# KUBODriver_Amp.net
KiCad netlist of a schematic drawn in Altium Designer
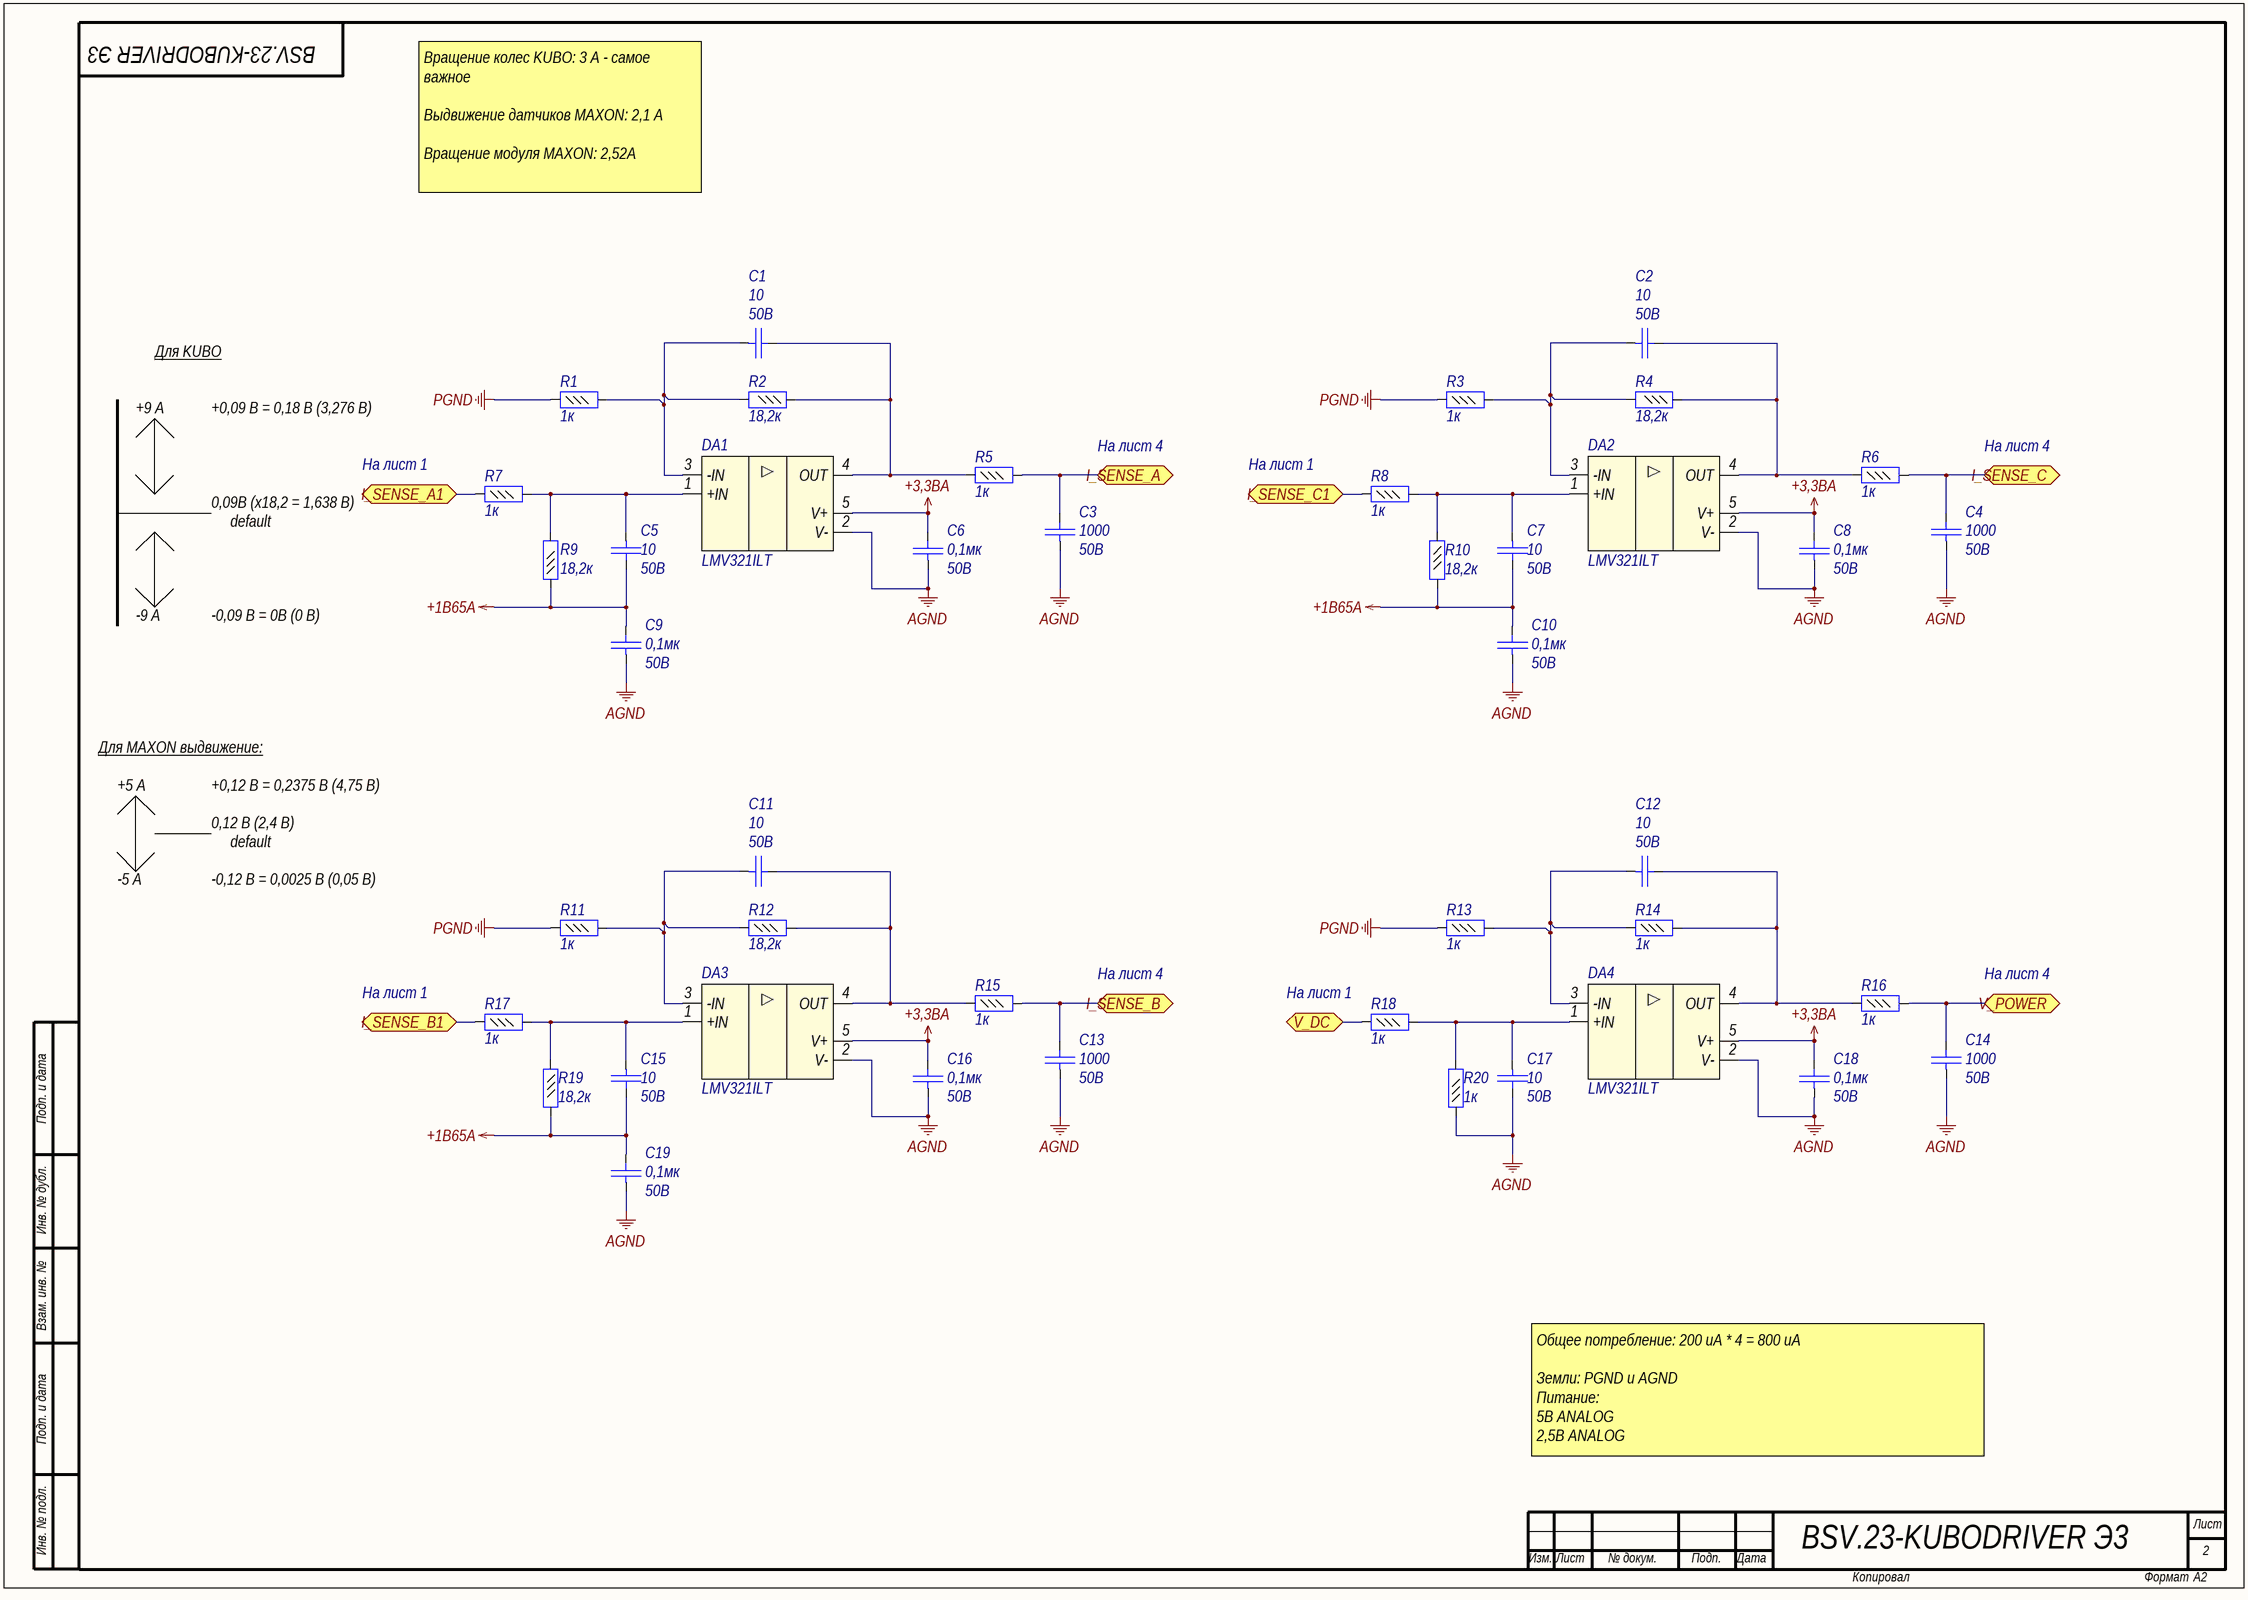
[diagram p0: KUBODriver_Amp.SchDoc]

(export (version "E")
  (design (tool "Eeschema 10.0.6"))
  (components
    (comp (ref "C1")
      (value "10")
      (footprint "C0402")
      (description "Конденсатор")
      (fields
        (field (name "VOLTAGE") "50B")
        (field (name "PART NUMBER") "GRM1535C1H100J")
        (field (name "Comment") "Capacitor")
      )
      (libsource (lib "MOP44") (part "Capacitor"))
    )
    (comp (ref "C2")
      (value "10")
      (footprint "C0402")
      (description "Конденсатор")
      (fields
        (field (name "VOLTAGE") "50B")
        (field (name "PART NUMBER") "GRM1535C1H100J")
        (field (name "Comment") "Capacitor")
      )
      (libsource (lib "MOP44") (part "Capacitor"))
    )
    (comp (ref "C3")
      (value "1000")
      (footprint "C0402")
      (description "Конденсатор")
      (fields
        (field (name "VOLTAGE") "50B")
        (field (name "PART NUMBER") "GRM1555C1H102J")
        (field (name "Comment") "Capacitor")
      )
      (libsource (lib "MOP44") (part "Capacitor"))
    )
    (comp (ref "C4")
      (value "1000")
      (footprint "C0402")
      (description "Конденсатор")
      (fields
        (field (name "VOLTAGE") "50B")
        (field (name "PART NUMBER") "GRM1555C1H102J")
        (field (name "Comment") "Capacitor")
      )
      (libsource (lib "MOP44") (part "Capacitor"))
    )
    (comp (ref "C5")
      (value "10")
      (footprint "C0402")
      (description "Конденсатор")
      (fields
        (field (name "VOLTAGE") "50B")
        (field (name "PART NUMBER") "GRM1535C1H100J")
        (field (name "Comment") "Capacitor")
      )
      (libsource (lib "MOP44") (part "Capacitor"))
    )
    (comp (ref "C6")
      (value "0,1мк")
      (footprint "C0402")
      (description "Конденсатор")
      (fields
        (field (name "VOLTAGE") "50В")
        (field (name "PART NUMBER") "GRM155R71H104KE14D ")
        (field (name "Comment") "Capacitor")
      )
      (libsource (lib "MOP44") (part "Capacitor"))
    )
    (comp (ref "C7")
      (value "10")
      (footprint "C0402")
      (description "Конденсатор")
      (fields
        (field (name "VOLTAGE") "50B")
        (field (name "PART NUMBER") "GRM1535C1H100J")
        (field (name "Comment") "Capacitor")
      )
      (libsource (lib "MOP44") (part "Capacitor"))
    )
    (comp (ref "C8")
      (value "0,1мк")
      (footprint "C0402")
      (description "Конденсатор")
      (fields
        (field (name "VOLTAGE") "50В")
        (field (name "PART NUMBER") "GRM155R71H104KE14D ")
        (field (name "Comment") "Capacitor")
      )
      (libsource (lib "MOP44") (part "Capacitor"))
    )
    (comp (ref "C9")
      (value "0,1мк")
      (footprint "C0402")
      (description "Конденсатор")
      (fields
        (field (name "VOLTAGE") "50В")
        (field (name "PART NUMBER") "GRM155R71H104KE14D ")
        (field (name "Comment") "Capacitor")
      )
      (libsource (lib "MOP44") (part "Capacitor"))
    )
    (comp (ref "C10")
      (value "0,1мк")
      (footprint "C0402")
      (description "Конденсатор")
      (fields
        (field (name "VOLTAGE") "50В")
        (field (name "PART NUMBER") "GRM155R71H104KE14D ")
        (field (name "Comment") "Capacitor")
      )
      (libsource (lib "MOP44") (part "Capacitor"))
    )
    (comp (ref "C11")
      (value "10")
      (footprint "C0402")
      (description "Конденсатор")
      (fields
        (field (name "VOLTAGE") "50B")
        (field (name "PART NUMBER") "GRM1535C1H100J")
        (field (name "Comment") "Capacitor")
      )
      (libsource (lib "MOP44") (part "Capacitor"))
    )
    (comp (ref "C12")
      (value "10")
      (footprint "C0402")
      (description "Конденсатор")
      (fields
        (field (name "VOLTAGE") "50B")
        (field (name "PART NUMBER") "GRM1535C1H100J")
        (field (name "Comment") "Capacitor")
      )
      (libsource (lib "MOP44") (part "Capacitor"))
    )
    (comp (ref "C13")
      (value "1000")
      (footprint "C0402")
      (description "Конденсатор")
      (fields
        (field (name "VOLTAGE") "50B")
        (field (name "PART NUMBER") "GRM1555C1H102J")
        (field (name "Comment") "Capacitor")
      )
      (libsource (lib "MOP44") (part "Capacitor"))
    )
    (comp (ref "C14")
      (value "1000")
      (footprint "C0402")
      (description "Конденсатор")
      (fields
        (field (name "VOLTAGE") "50B")
        (field (name "PART NUMBER") "GRM1555C1H102J")
        (field (name "Comment") "Capacitor")
      )
      (libsource (lib "MOP44") (part "Capacitor"))
    )
    (comp (ref "C15")
      (value "10")
      (footprint "C0402")
      (description "Конденсатор")
      (fields
        (field (name "VOLTAGE") "50B")
        (field (name "PART NUMBER") "GRM1535C1H100J")
        (field (name "Comment") "Capacitor")
      )
      (libsource (lib "MOP44") (part "Capacitor"))
    )
    (comp (ref "C16")
      (value "0,1мк")
      (footprint "C0402")
      (description "Конденсатор")
      (fields
        (field (name "VOLTAGE") "50В")
        (field (name "PART NUMBER") "GRM155R71H104KE14D ")
        (field (name "Comment") "Capacitor")
      )
      (libsource (lib "MOP44") (part "Capacitor"))
    )
    (comp (ref "C17")
      (value "10")
      (footprint "C0402")
      (description "Конденсатор")
      (fields
        (field (name "VOLTAGE") "50B")
        (field (name "PART NUMBER") "GRM1535C1H100J")
        (field (name "Comment") "Capacitor")
      )
      (libsource (lib "MOP44") (part "Capacitor"))
    )
    (comp (ref "C18")
      (value "0,1мк")
      (footprint "C0402")
      (description "Конденсатор")
      (fields
        (field (name "VOLTAGE") "50В")
        (field (name "PART NUMBER") "GRM155R71H104KE14D ")
        (field (name "Comment") "Capacitor")
      )
      (libsource (lib "MOP44") (part "Capacitor"))
    )
    (comp (ref "C19")
      (value "0,1мк")
      (footprint "C0402")
      (description "Конденсатор")
      (fields
        (field (name "VOLTAGE") "50В")
        (field (name "PART NUMBER") "GRM155R71H104KE14D ")
        (field (name "Comment") "Capacitor")
      )
      (libsource (lib "MOP44") (part "Capacitor"))
    )
    (comp (ref "DA1")
      (value "LMV321ILT")
      (footprint "SOT23-5")
      (description "HIGH-DRIVE OPERATIONAL AMPLIFIERS WITH SHUTDOWN")
      (libsource (lib "MOP44") (part "LMV321ILT"))
    )
    (comp (ref "DA2")
      (value "LMV321ILT")
      (footprint "SOT23-5")
      (description "HIGH-DRIVE OPERATIONAL AMPLIFIERS WITH SHUTDOWN")
      (libsource (lib "MOP44") (part "LMV321ILT"))
    )
    (comp (ref "DA3")
      (value "LMV321ILT")
      (footprint "SOT23-5")
      (description "HIGH-DRIVE OPERATIONAL AMPLIFIERS WITH SHUTDOWN")
      (libsource (lib "MOP44") (part "LMV321ILT"))
    )
    (comp (ref "DA4")
      (value "LMV321ILT")
      (footprint "SOT23-5")
      (description "HIGH-DRIVE OPERATIONAL AMPLIFIERS WITH SHUTDOWN")
      (libsource (lib "MOP44") (part "LMV321ILT"))
    )
    (comp (ref "R1")
      (value "1к")
      (footprint "R0402")
      (description "Резистор")
      (fields (field (name "PART NUMBER") "RC0402FR-071KL") (field (name "POWER") "0,062Вт"))
      (libsource (lib "MOP44") (part "Resistor_0,062Вт"))
    )
    (comp (ref "R2")
      (value "18,2к")
      (footprint "R0402")
      (description "Резистор")
      (fields (field (name "PART NUMBER") "RC0402FR-0718K2L") (field (name "POWER") "0,062Вт"))
      (libsource (lib "") (part "Resistor_0,062Вт_1"))
    )
    (comp (ref "R3")
      (value "1к")
      (footprint "R0402")
      (description "Резистор")
      (fields (field (name "PART NUMBER") "RC0402FR-071KL") (field (name "POWER") "0,062Вт"))
      (libsource (lib "MOP44") (part "Resistor_0,062Вт"))
    )
    (comp (ref "R4")
      (value "18,2к")
      (footprint "R0402")
      (description "Резистор")
      (fields (field (name "PART NUMBER") "RC0402FR-0718K2L") (field (name "POWER") "0,062Вт"))
      (libsource (lib "") (part "Resistor_0,062Вт_1"))
    )
    (comp (ref "R5")
      (value "1к")
      (footprint "R0402")
      (description "Резистор")
      (fields (field (name "PART NUMBER") "RC0402FR-071KL") (field (name "POWER") "0,062Вт"))
      (libsource (lib "MOP44") (part "Resistor_0,062Вт"))
    )
    (comp (ref "R6")
      (value "1к")
      (footprint "R0402")
      (description "Резистор")
      (fields (field (name "PART NUMBER") "RC0402FR-071KL") (field (name "POWER") "0,062Вт"))
      (libsource (lib "MOP44") (part "Resistor_0,062Вт"))
    )
    (comp (ref "R7")
      (value "1к")
      (footprint "R0402")
      (description "Резистор")
      (fields (field (name "PART NUMBER") "RC0402FR-071KL") (field (name "POWER") "0,062Вт"))
      (libsource (lib "MOP44") (part "Resistor_0,062Вт"))
    )
    (comp (ref "R8")
      (value "1к")
      (footprint "R0402")
      (description "Резистор")
      (fields (field (name "PART NUMBER") "RC0402FR-071KL") (field (name "POWER") "0,062Вт"))
      (libsource (lib "MOP44") (part "Resistor_0,062Вт"))
    )
    (comp (ref "R9")
      (value "18,2к")
      (footprint "R0402")
      (description "Резистор")
      (fields (field (name "PART NUMBER") "RC0402FR-0718K2L") (field (name "POWER") "0,062Вт"))
      (libsource (lib "") (part "Resistor_0,062Вт_3"))
    )
    (comp (ref "R10")
      (value "18,2к")
      (footprint "R0402")
      (description "Резистор")
      (fields (field (name "PART NUMBER") "RC0402FR-0718K2L") (field (name "POWER") "0,062Вт"))
      (libsource (lib "") (part "Resistor_0,062Вт_2"))
    )
    (comp (ref "R11")
      (value "1к")
      (footprint "R0402")
      (description "Резистор")
      (fields (field (name "PART NUMBER") "RC0402FR-071KL") (field (name "POWER") "0,062Вт"))
      (libsource (lib "MOP44") (part "Resistor_0,062Вт"))
    )
    (comp (ref "R12")
      (value "18,2к")
      (footprint "R0402")
      (description "Резистор")
      (fields (field (name "PART NUMBER") "RC0402FR-0718K2L") (field (name "POWER") "0,062Вт"))
      (libsource (lib "MOP44") (part "Resistor_0,062Вт"))
    )
    (comp (ref "R13")
      (value "1к")
      (footprint "R0402")
      (description "Резистор")
      (fields (field (name "PART NUMBER") "RC0402FR-071KL") (field (name "POWER") "0,062Вт"))
      (libsource (lib "MOP44") (part "Resistor_0,062Вт"))
    )
    (comp (ref "R14")
      (value "1к")
      (footprint "R0402")
      (description "Резистор")
      (fields (field (name "PART NUMBER") "RC0402FR-071KL") (field (name "POWER") "0,062Вт"))
      (libsource (lib "MOP44") (part "Resistor_0,062Вт"))
    )
    (comp (ref "R15")
      (value "1к")
      (footprint "R0402")
      (description "Резистор")
      (fields (field (name "PART NUMBER") "RC0402FR-071KL") (field (name "POWER") "0,062Вт"))
      (libsource (lib "MOP44") (part "Resistor_0,062Вт"))
    )
    (comp (ref "R16")
      (value "1к")
      (footprint "R0402")
      (description "Резистор")
      (fields (field (name "PART NUMBER") "RC0402FR-071KL") (field (name "POWER") "0,062Вт"))
      (libsource (lib "MOP44") (part "Resistor_0,062Вт"))
    )
    (comp (ref "R17")
      (value "1к")
      (footprint "R0402")
      (description "Резистор")
      (fields (field (name "PART NUMBER") "RC0402FR-071KL") (field (name "POWER") "0,062Вт"))
      (libsource (lib "MOP44") (part "Resistor_0,062Вт"))
    )
    (comp (ref "R18")
      (value "1к")
      (footprint "R0402")
      (description "Резистор")
      (fields (field (name "PART NUMBER") "RC0402FR-071KL") (field (name "POWER") "0,062Вт"))
      (libsource (lib "MOP44") (part "Resistor_0,062Вт"))
    )
    (comp (ref "R19")
      (value "18,2к")
      (footprint "R0402")
      (description "Резистор")
      (fields (field (name "PART NUMBER") "RC0402FR-0718K2L") (field (name "POWER") "0,062Вт"))
      (libsource (lib "") (part "Resistor_0,062Вт_2"))
    )
    (comp (ref "R20")
      (value "1к")
      (footprint "R0402")
      (description "Резистор")
      (fields (field (name "PART NUMBER") "RC0402FR-071KL") (field (name "POWER") "0,062Вт"))
      (libsource (lib "") (part "Resistor_0,062Вт_3"))
    )
  )
  (nets
    (net (code "1") (name "+1B65A") (class "Default")
      (node (ref "C10") (pin "2") (pinfunction "2_2") (pintype "passive"))
      (node (ref "C15") (pin "2") (pinfunction "2_2") (pintype "passive"))
      (node (ref "C19") (pin "2") (pinfunction "2_2") (pintype "passive"))
      (node (ref "C5") (pin "2") (pinfunction "2_2") (pintype "passive"))
      (node (ref "C7") (pin "2") (pinfunction "2_2") (pintype "passive"))
      (node (ref "C9") (pin "2") (pinfunction "2_2") (pintype "passive"))
      (node (ref "R10") (pin "2") (pinfunction "2_2") (pintype "passive"))
      (node (ref "R19") (pin "2") (pinfunction "2_2") (pintype "passive"))
      (node (ref "R9") (pin "1") (pinfunction "1_1") (pintype "passive"))
    )
    (net (code "2") (name "+3,3BA") (class "Default")
      (node (ref "C16") (pin "2") (pinfunction "2_2") (pintype "passive"))
      (node (ref "C18") (pin "2") (pinfunction "2_2") (pintype "passive"))
      (node (ref "C6") (pin "2") (pinfunction "2_2") (pintype "passive"))
      (node (ref "C8") (pin "2") (pinfunction "2_2") (pintype "passive"))
      (node (ref "DA1") (pin "5") (pinfunction "V+_5") (pintype "passive"))
      (node (ref "DA2") (pin "5") (pinfunction "V+_5") (pintype "passive"))
      (node (ref "DA3") (pin "5") (pinfunction "V+_5") (pintype "passive"))
      (node (ref "DA4") (pin "5") (pinfunction "V+_5") (pintype "passive"))
    )
    (net (code "3") (name "/I_SENSE_A") (class "Default")
      (node (ref "C3") (pin "2") (pinfunction "2_2") (pintype "passive"))
      (node (ref "R5") (pin "2") (pinfunction "2_2") (pintype "passive"))
    )
    (net (code "4") (name "/I_SENSE_A1") (class "Default")
      (node (ref "R7") (pin "1") (pinfunction "1_1") (pintype "passive"))
    )
    (net (code "5") (name "/I_SENSE_B") (class "Default")
      (node (ref "C13") (pin "2") (pinfunction "2_2") (pintype "passive"))
      (node (ref "R15") (pin "2") (pinfunction "2_2") (pintype "passive"))
    )
    (net (code "6") (name "/I_SENSE_B1") (class "Default")
      (node (ref "R17") (pin "1") (pinfunction "1_1") (pintype "passive"))
    )
    (net (code "7") (name "/I_SENSE_C") (class "Default")
      (node (ref "C4") (pin "2") (pinfunction "2_2") (pintype "passive"))
      (node (ref "R6") (pin "2") (pinfunction "2_2") (pintype "passive"))
    )
    (net (code "8") (name "/I_SENSE_C1") (class "Default")
      (node (ref "R8") (pin "1") (pinfunction "1_1") (pintype "passive"))
    )
    (net (code "9") (name "/V_DC") (class "Default")
      (node (ref "R18") (pin "1") (pinfunction "1_1") (pintype "passive"))
    )
    (net (code "10") (name "/V_POWER") (class "Default")
      (node (ref "C14") (pin "2") (pinfunction "2_2") (pintype "passive"))
      (node (ref "R16") (pin "2") (pinfunction "2_2") (pintype "passive"))
    )
    (net (code "11") (name "AGND") (class "Default")
      (node (ref "C10") (pin "1") (pinfunction "1_1") (pintype "passive"))
      (node (ref "C13") (pin "1") (pinfunction "1_1") (pintype "passive"))
      (node (ref "C14") (pin "1") (pinfunction "1_1") (pintype "passive"))
      (node (ref "C16") (pin "1") (pinfunction "1_1") (pintype "passive"))
      (node (ref "C17") (pin "2") (pinfunction "2_2") (pintype "passive"))
      (node (ref "C18") (pin "1") (pinfunction "1_1") (pintype "passive"))
      (node (ref "C19") (pin "1") (pinfunction "1_1") (pintype "passive"))
      (node (ref "C3") (pin "1") (pinfunction "1_1") (pintype "passive"))
      (node (ref "C4") (pin "1") (pinfunction "1_1") (pintype "passive"))
      (node (ref "C6") (pin "1") (pinfunction "1_1") (pintype "passive"))
      (node (ref "C8") (pin "1") (pinfunction "1_1") (pintype "passive"))
      (node (ref "C9") (pin "1") (pinfunction "1_1") (pintype "passive"))
      (node (ref "DA1") (pin "2") (pinfunction "V-_2") (pintype "passive"))
      (node (ref "DA2") (pin "2") (pinfunction "V-_2") (pintype "passive"))
      (node (ref "DA3") (pin "2") (pinfunction "V-_2") (pintype "passive"))
      (node (ref "DA4") (pin "2") (pinfunction "V-_2") (pintype "passive"))
      (node (ref "R20") (pin "1") (pinfunction "1_1") (pintype "passive"))
    )
    (net (code "12") (name "Net-(DA1-+IN)") (class "Default")
      (node (ref "C5") (pin "1") (pinfunction "1_1") (pintype "passive"))
      (node (ref "DA1") (pin "1") (pinfunction "+IN_1") (pintype "passive"))
      (node (ref "R7") (pin "2") (pinfunction "2_2") (pintype "passive"))
      (node (ref "R9") (pin "2") (pinfunction "2_2") (pintype "passive"))
    )
    (net (code "13") (name "Net-(DA1--IN)") (class "Default")
      (node (ref "C1") (pin "1") (pinfunction "1_1") (pintype "passive"))
      (node (ref "DA1") (pin "3") (pinfunction "-IN_3") (pintype "passive"))
      (node (ref "R1") (pin "2") (pinfunction "2_2") (pintype "passive"))
      (node (ref "R2") (pin "2") (pinfunction "2_2") (pintype "passive"))
    )
    (net (code "14") (name "Net-(DA1-OUT)") (class "Default")
      (node (ref "C1") (pin "2") (pinfunction "2_2") (pintype "passive"))
      (node (ref "DA1") (pin "4") (pinfunction "OUT_4") (pintype "passive"))
      (node (ref "R2") (pin "1") (pinfunction "1_1") (pintype "passive"))
      (node (ref "R5") (pin "1") (pinfunction "1_1") (pintype "passive"))
    )
    (net (code "15") (name "Net-(DA2-+IN)") (class "Default")
      (node (ref "C7") (pin "1") (pinfunction "1_1") (pintype "passive"))
      (node (ref "DA2") (pin "1") (pinfunction "+IN_1") (pintype "passive"))
      (node (ref "R10") (pin "1") (pinfunction "1_1") (pintype "passive"))
      (node (ref "R8") (pin "2") (pinfunction "2_2") (pintype "passive"))
    )
    (net (code "16") (name "Net-(DA2--IN)") (class "Default")
      (node (ref "C2") (pin "1") (pinfunction "1_1") (pintype "passive"))
      (node (ref "DA2") (pin "3") (pinfunction "-IN_3") (pintype "passive"))
      (node (ref "R3") (pin "2") (pinfunction "2_2") (pintype "passive"))
      (node (ref "R4") (pin "2") (pinfunction "2_2") (pintype "passive"))
    )
    (net (code "17") (name "Net-(DA2-OUT)") (class "Default")
      (node (ref "C2") (pin "2") (pinfunction "2_2") (pintype "passive"))
      (node (ref "DA2") (pin "4") (pinfunction "OUT_4") (pintype "passive"))
      (node (ref "R4") (pin "1") (pinfunction "1_1") (pintype "passive"))
      (node (ref "R6") (pin "1") (pinfunction "1_1") (pintype "passive"))
    )
    (net (code "18") (name "Net-(DA3-+IN)") (class "Default")
      (node (ref "C15") (pin "1") (pinfunction "1_1") (pintype "passive"))
      (node (ref "DA3") (pin "1") (pinfunction "+IN_1") (pintype "passive"))
      (node (ref "R17") (pin "2") (pinfunction "2_2") (pintype "passive"))
      (node (ref "R19") (pin "1") (pinfunction "1_1") (pintype "passive"))
    )
    (net (code "19") (name "Net-(DA3--IN)") (class "Default")
      (node (ref "C11") (pin "1") (pinfunction "1_1") (pintype "passive"))
      (node (ref "DA3") (pin "3") (pinfunction "-IN_3") (pintype "passive"))
      (node (ref "R11") (pin "2") (pinfunction "2_2") (pintype "passive"))
      (node (ref "R12") (pin "1") (pinfunction "1_1") (pintype "passive"))
    )
    (net (code "20") (name "Net-(DA3-OUT)") (class "Default")
      (node (ref "C11") (pin "2") (pinfunction "2_2") (pintype "passive"))
      (node (ref "DA3") (pin "4") (pinfunction "OUT_4") (pintype "passive"))
      (node (ref "R12") (pin "2") (pinfunction "2_2") (pintype "passive"))
      (node (ref "R15") (pin "1") (pinfunction "1_1") (pintype "passive"))
    )
    (net (code "21") (name "Net-(DA4-+IN)") (class "Default")
      (node (ref "C17") (pin "1") (pinfunction "1_1") (pintype "passive"))
      (node (ref "DA4") (pin "1") (pinfunction "+IN_1") (pintype "passive"))
      (node (ref "R18") (pin "2") (pinfunction "2_2") (pintype "passive"))
      (node (ref "R20") (pin "2") (pinfunction "2_2") (pintype "passive"))
    )
    (net (code "22") (name "Net-(DA4--IN)") (class "Default")
      (node (ref "C12") (pin "1") (pinfunction "1_1") (pintype "passive"))
      (node (ref "DA4") (pin "3") (pinfunction "-IN_3") (pintype "passive"))
      (node (ref "R13") (pin "2") (pinfunction "2_2") (pintype "passive"))
      (node (ref "R14") (pin "1") (pinfunction "1_1") (pintype "passive"))
    )
    (net (code "23") (name "Net-(DA4-OUT)") (class "Default")
      (node (ref "C12") (pin "2") (pinfunction "2_2") (pintype "passive"))
      (node (ref "DA4") (pin "4") (pinfunction "OUT_4") (pintype "passive"))
      (node (ref "R14") (pin "2") (pinfunction "2_2") (pintype "passive"))
      (node (ref "R16") (pin "1") (pinfunction "1_1") (pintype "passive"))
    )
    (net (code "24") (name "PGND") (class "Default")
      (node (ref "R1") (pin "1") (pinfunction "1_1") (pintype "passive"))
      (node (ref "R11") (pin "1") (pinfunction "1_1") (pintype "passive"))
      (node (ref "R13") (pin "1") (pinfunction "1_1") (pintype "passive"))
      (node (ref "R3") (pin "1") (pinfunction "1_1") (pintype "passive"))
    )
  )
)
